# battery_volt_sense.net
KiCad netlist of a schematic drawn in Altium Designer
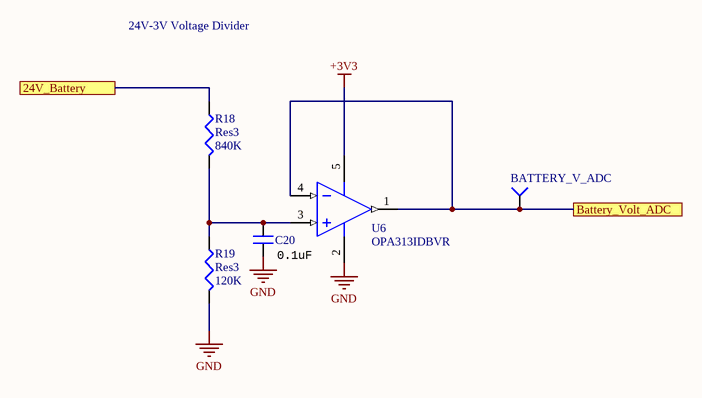
[diagram p0: battery_volt_sense.SchDoc]

(export (version "E")
  (design (tool "Eeschema 10.0.6"))
  (components
    (comp (ref "BATTERY_V_ADC")
      (value "BATTERY_V_ADC")
      (footprint "TESTPOINT")
      (description "TESTPOINT_SMD")
      (libsource (lib "UWRT_Schematic_Library_2020") (part "TESTPOINT_SMD"))
    )
    (comp (ref "C20")
      (value "0.1uF")
      (footprint "CAPC0603(1608)55_N")
      (description "CAP CER 0.1UF 16V X7R 0603")
      (fields (field (name "MPN") "CC0603KRX7R7BB104") (field (name "MANUFACTURER") "Yageo"))
      (libsource (lib "*") (part "CAP_0.1uF_16V_0603"))
    )
    (comp (ref "R18")
      (value "Res3")
      (footprint "J1-0603")
      (description "Resistor")
      (fields (field (name "ALTIUM_VALUE") "840K") (field (name "PUBLISHER") "Altium Limited"))
      (libsource (lib "Miscellaneous Devices") (part "Res3"))
    )
    (comp (ref "R19")
      (value "Res3")
      (footprint "J1-0603")
      (description "Resistor")
      (fields (field (name "ALTIUM_VALUE") "120K") (field (name "PUBLISHER") "Altium Limited"))
      (libsource (lib "Miscellaneous Devices") (part "Res3"))
    )
    (comp (ref "U6")
      (value "OPA313IDBVR")
      (footprint "DBV0005A_M")
      (fields
        (field (name "MANUFACTURER") "Texas Instruments")
        (field (name "DIGI-KEY PART NUMBER") "296-35607-1-ND")
      )
      (libsource (lib "UWRT_Schematic_Library_2020") (part "OPAMP"))
    )
  )
  (nets
    (net (code "1") (name "+3V3") (class "Default")
      (node (ref "U6") (pin "5") (pinfunction "V+_5") (pintype "power_in"))
    )
    (net (code "2") (name "/24V_Battery") (class "Default")
      (node (ref "R18") (pin "1") (pinfunction "1_1") (pintype "passive"))
    )
    (net (code "3") (name "/Battery_Volt_ADC") (class "Default")
      (node (ref "BATTERY_V_ADC") (pin "1") (pinfunction "=value_1") (pintype "passive"))
      (node (ref "U6") (pin "1") (pinfunction "OUT_1") (pintype "output"))
      (node (ref "U6") (pin "4") (pinfunction "IN-_4") (pintype "input"))
    )
    (net (code "4") (name "GND") (class "Default")
      (node (ref "C20") (pin "1") (pinfunction "1_1") (pintype "passive"))
      (node (ref "R19") (pin "2") (pinfunction "2_2") (pintype "passive"))
      (node (ref "U6") (pin "2") (pinfunction "V-_2") (pintype "power_in"))
    )
    (net (code "5") (name "Net-(U6-IN+)") (class "Default")
      (node (ref "C20") (pin "2") (pinfunction "2_2") (pintype "passive"))
      (node (ref "R18") (pin "2") (pinfunction "2_2") (pintype "passive"))
      (node (ref "R19") (pin "1") (pinfunction "1_1") (pintype "passive"))
      (node (ref "U6") (pin "3") (pinfunction "IN+_3") (pintype "input"))
    )
  )
)
